# Power_Supply.net
KiCad netlist of a schematic drawn in Altium Designer
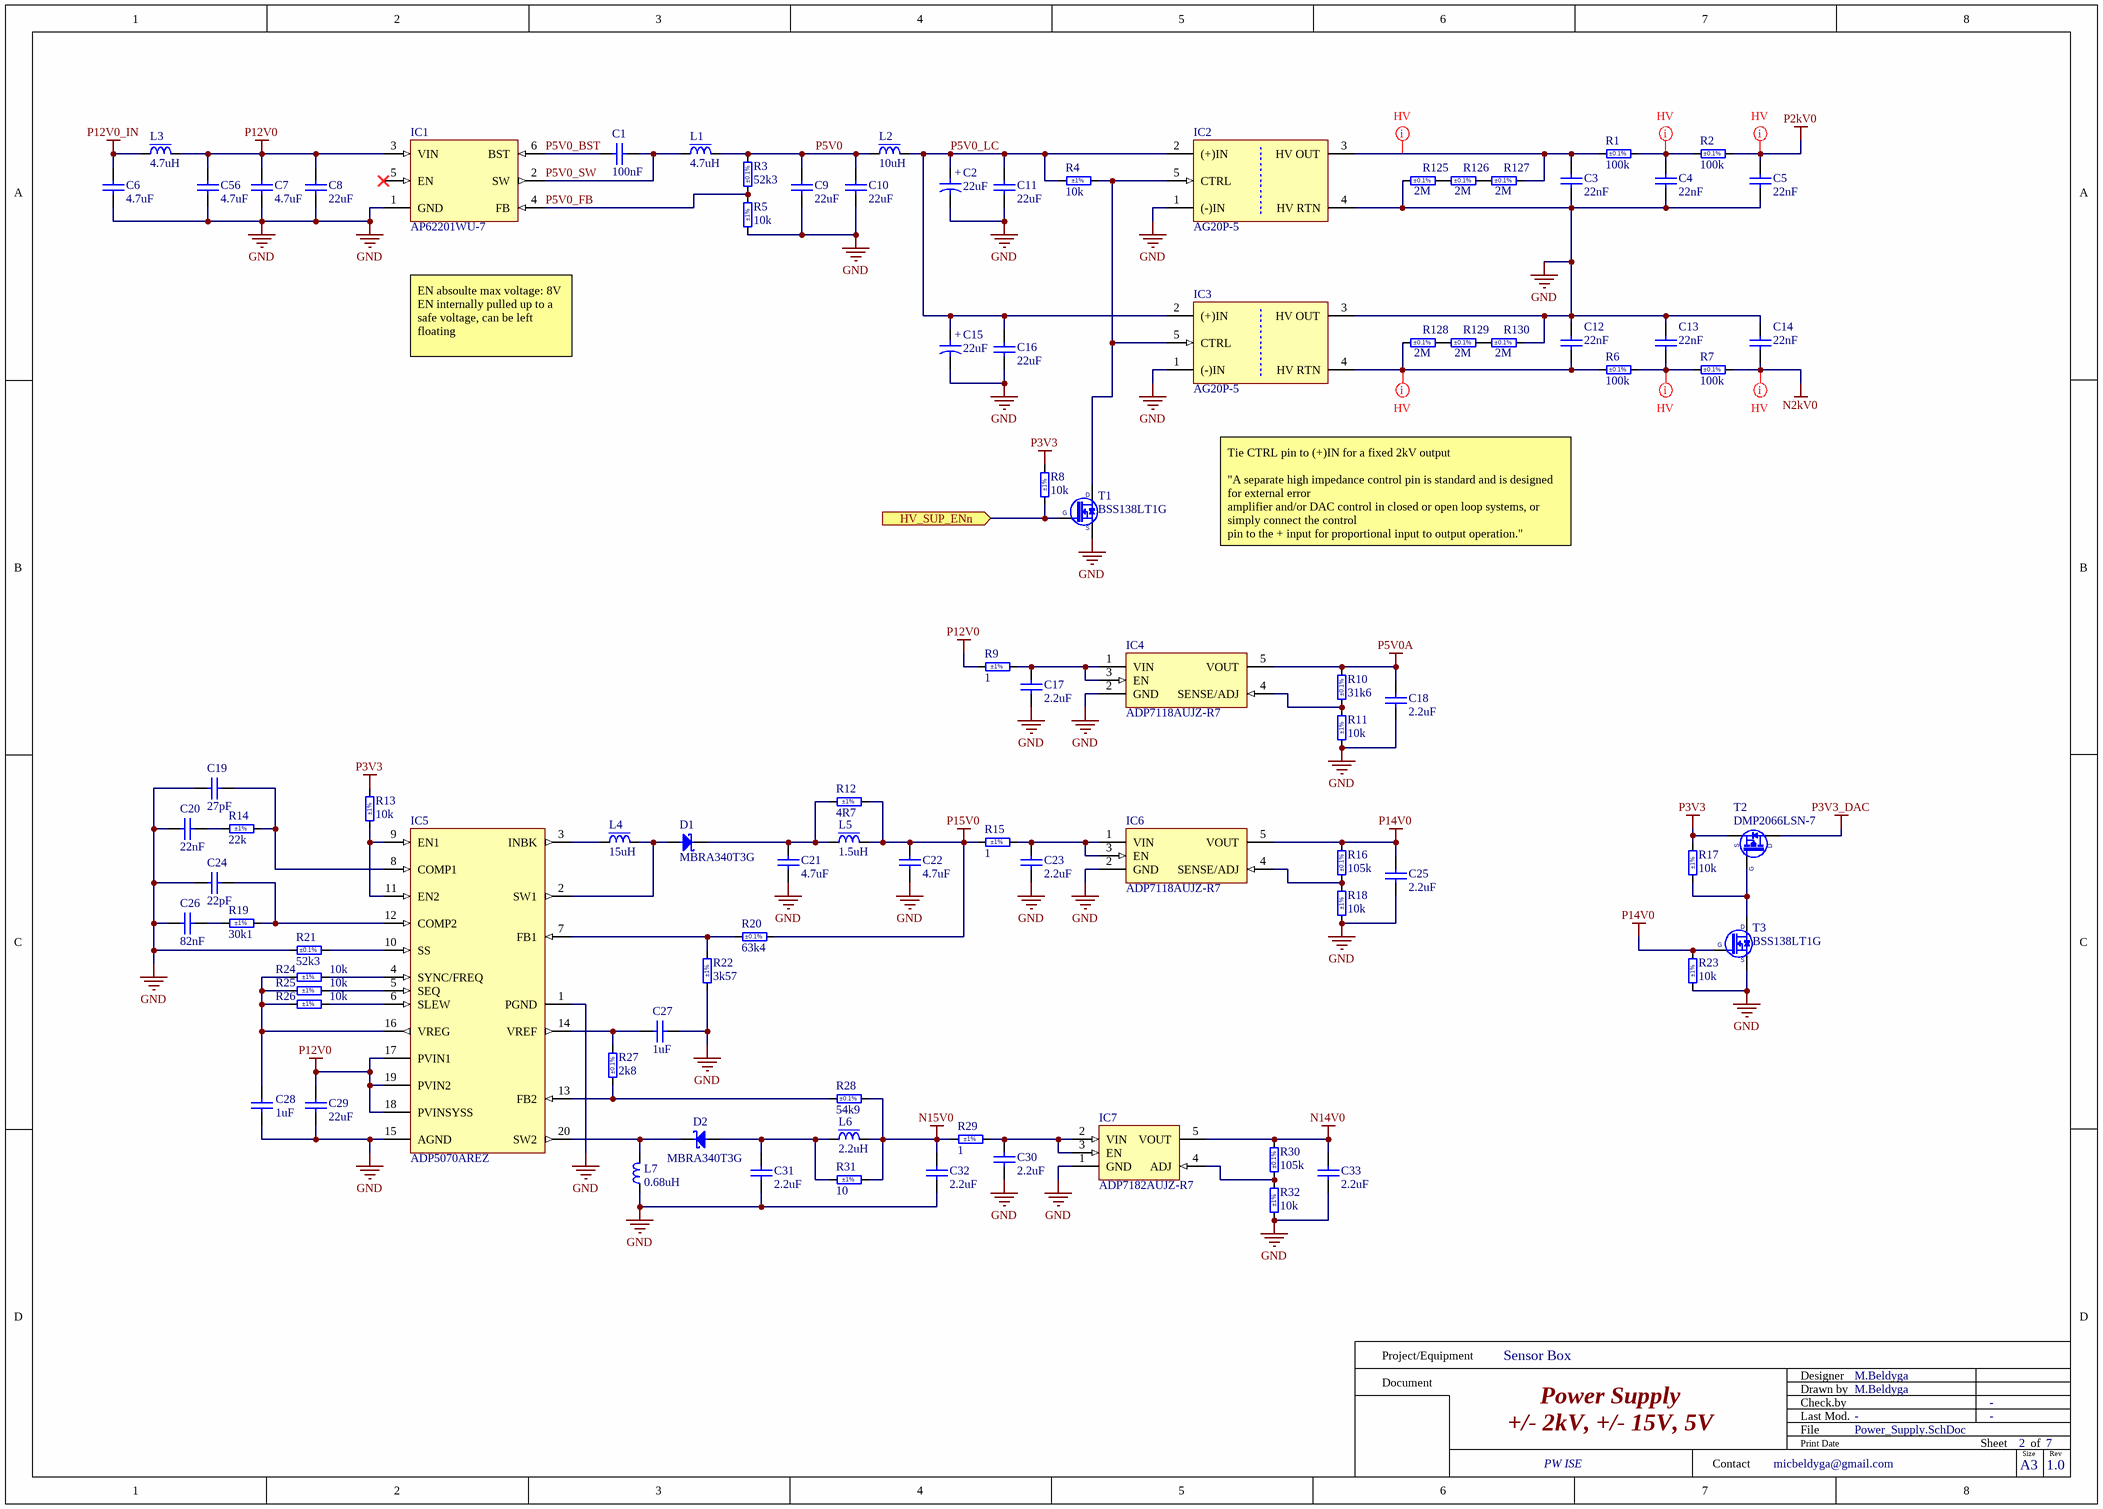
[diagram p0: Power_Supply.SchDoc]

(export (version "E")
  (design (tool "Eeschema 10.0.6"))
  (components
    (comp (ref "C1")
      (value "100nF")
      (footprint "CAPC1005X55N")
      (description "Non-polarised capacitor")
      (fields
        (field (name "PART NUMBER") "CC0402_100NF_50V_10%_X7R")
        (field (name "VOLTAGE") "50V")
        (field (name "AUTHOR") "CERN DEM MR")
      )
      (libsource (lib "Capacitors") (part "Capacitor - non polarized"))
    )
    (comp (ref "C2")
      (value "22uF")
      (footprint "CAPMP3528X210N")
      (description "Polarised capacitor")
      (fields
        (field (name "PART NUMBER") "CTE3528-21_22UF_20V_10%")
        (field (name "VOLTAGE") "20V")
        (field (name "AUTHOR") "CERN DEM JLC")
      )
      (libsource (lib "Capacitors") (part "Capacitor - polarized"))
    )
    (comp (ref "C3")
      (value "22nF")
      (footprint "CAPC5764X279N")
      (description "Non-polarised capacitor")
      (fields
        (field (name "PART NUMBER") "CC2225_22NF_2.5KV_10%_X7R")
        (field (name "VOLTAGE") "2.5KV")
        (field (name "AUTHOR") "CERN DEM JLC")
      )
      (libsource (lib "Capacitors") (part "Capacitor - non polarized"))
    )
    (comp (ref "C4")
      (value "22nF")
      (footprint "CAPC5764X279N")
      (description "Non-polarised capacitor")
      (fields
        (field (name "PART NUMBER") "CC2225_22NF_2.5KV_10%_X7R")
        (field (name "VOLTAGE") "2.5KV")
        (field (name "AUTHOR") "CERN DEM JLC")
      )
      (libsource (lib "Capacitors") (part "Capacitor - non polarized"))
    )
    (comp (ref "C5")
      (value "22nF")
      (footprint "CAPC5764X279N")
      (description "Non-polarised capacitor")
      (fields
        (field (name "PART NUMBER") "CC2225_22NF_2.5KV_10%_X7R")
        (field (name "VOLTAGE") "2.5KV")
        (field (name "AUTHOR") "CERN DEM JLC")
      )
      (libsource (lib "Capacitors") (part "Capacitor - non polarized"))
    )
    (comp (ref "C6")
      (value "4.7uF")
      (footprint "CAPC2012X145N")
      (description "Non-polarised capacitor")
      (fields
        (field (name "PART NUMBER") "CC0805_4.7UF_50V_10%_X7R")
        (field (name "VOLTAGE") "50V")
        (field (name "AUTHOR") "CERN DEM JMW")
      )
      (libsource (lib "Capacitors") (part "Capacitor - non polarized"))
    )
    (comp (ref "C7")
      (value "4.7uF")
      (footprint "CAPC2012X145N")
      (description "Non-polarised capacitor")
      (fields
        (field (name "PART NUMBER") "CC0805_4.7UF_50V_10%_X7R")
        (field (name "VOLTAGE") "50V")
        (field (name "AUTHOR") "CERN DEM JMW")
      )
      (libsource (lib "Capacitors") (part "Capacitor - non polarized"))
    )
    (comp (ref "C8")
      (value "22uF")
      (footprint "CAPC3216X180N")
      (description "Non-polarised capacitor")
      (fields
        (field (name "PART NUMBER") "CC1206_22UF_25V_20%_X5R")
        (field (name "VOLTAGE") "25V")
        (field (name "AUTHOR") "CERN DEM WB")
      )
      (libsource (lib "Capacitors") (part "Capacitor - non polarized"))
    )
    (comp (ref "C9")
      (value "22uF")
      (footprint "CAPC2012X135N")
      (description "Non-polarised capacitor")
      (fields
        (field (name "PART NUMBER") "CC0805_22UF_16V_10%_X5R")
        (field (name "VOLTAGE") "16V")
        (field (name "AUTHOR") "CERN DEM JLC")
      )
      (libsource (lib "Capacitors") (part "Capacitor - non polarized"))
    )
    (comp (ref "C10")
      (value "22uF")
      (footprint "CAPC2012X135N")
      (description "Non-polarised capacitor")
      (fields
        (field (name "PART NUMBER") "CC0805_22UF_16V_10%_X5R")
        (field (name "VOLTAGE") "16V")
        (field (name "AUTHOR") "CERN DEM JLC")
      )
      (libsource (lib "Capacitors") (part "Capacitor - non polarized"))
    )
    (comp (ref "C11")
      (value "22uF")
      (footprint "CAPC3216X180N")
      (description "Non-polarised capacitor")
      (fields
        (field (name "PART NUMBER") "CC1206_22UF_25V_20%_X5R")
        (field (name "VOLTAGE") "25V")
        (field (name "AUTHOR") "CERN DEM WB")
      )
      (libsource (lib "Capacitors") (part "Capacitor - non polarized"))
    )
    (comp (ref "C12")
      (value "22nF")
      (footprint "CAPC5764X279N")
      (description "Non-polarised capacitor")
      (fields
        (field (name "PART NUMBER") "CC2225_22NF_2.5KV_10%_X7R")
        (field (name "VOLTAGE") "2.5KV")
        (field (name "AUTHOR") "CERN DEM JLC")
      )
      (libsource (lib "Capacitors") (part "Capacitor - non polarized"))
    )
    (comp (ref "C13")
      (value "22nF")
      (footprint "CAPC5764X279N")
      (description "Non-polarised capacitor")
      (fields
        (field (name "PART NUMBER") "CC2225_22NF_2.5KV_10%_X7R")
        (field (name "VOLTAGE") "2.5KV")
        (field (name "AUTHOR") "CERN DEM JLC")
      )
      (libsource (lib "Capacitors") (part "Capacitor - non polarized"))
    )
    (comp (ref "C14")
      (value "22nF")
      (footprint "CAPC5764X279N")
      (description "Non-polarised capacitor")
      (fields
        (field (name "PART NUMBER") "CC2225_22NF_2.5KV_10%_X7R")
        (field (name "VOLTAGE") "2.5KV")
        (field (name "AUTHOR") "CERN DEM JLC")
      )
      (libsource (lib "Capacitors") (part "Capacitor - non polarized"))
    )
    (comp (ref "C15")
      (value "22uF")
      (footprint "CAPMP3528X210N")
      (description "Polarised capacitor")
      (fields
        (field (name "PART NUMBER") "CTE3528-21_22UF_20V_10%")
        (field (name "VOLTAGE") "20V")
        (field (name "AUTHOR") "CERN DEM JLC")
      )
      (libsource (lib "Capacitors") (part "Capacitor - polarized"))
    )
    (comp (ref "C16")
      (value "22uF")
      (footprint "CAPC3216X180N")
      (description "Non-polarised capacitor")
      (fields
        (field (name "PART NUMBER") "CC1206_22UF_25V_20%_X5R")
        (field (name "VOLTAGE") "25V")
        (field (name "AUTHOR") "CERN DEM WB")
      )
      (libsource (lib "Capacitors") (part "Capacitor - non polarized"))
    )
    (comp (ref "C17")
      (value "2.2uF")
      (footprint "CAPC1005X55N")
      (description "Non-polarised capacitor")
      (fields
        (field (name "PART NUMBER") "CC0402_2.2UF_16V_10%_X5R")
        (field (name "VOLTAGE") "16V")
        (field (name "AUTHOR") "CERN DEM BC")
      )
      (libsource (lib "Capacitors") (part "Capacitor - non polarized"))
    )
    (comp (ref "C18")
      (value "2.2uF")
      (footprint "CAPC1005X55N")
      (description "Non-polarised capacitor")
      (fields
        (field (name "PART NUMBER") "CC0402_2.2UF_16V_10%_X5R")
        (field (name "VOLTAGE") "16V")
        (field (name "AUTHOR") "CERN DEM BC")
      )
      (libsource (lib "Capacitors") (part "Capacitor - non polarized"))
    )
    (comp (ref "C19")
      (value "27pF")
      (footprint "CAPC1005X55N")
      (description "Non-polarised capacitor")
      (fields
        (field (name "PART NUMBER") "CC0402_27PF_50V_5%_C0G")
        (field (name "VOLTAGE") "50V")
        (field (name "AUTHOR") "CERN DEM JLC")
      )
      (libsource (lib "Capacitors") (part "Capacitor - non polarized"))
    )
    (comp (ref "C20")
      (value "22nF")
      (footprint "CAPC1005X55N")
      (description "Non-polarised capacitor")
      (fields
        (field (name "PART NUMBER") "CC0402_22NF_16V_10%_X7R")
        (field (name "VOLTAGE") "16V")
        (field (name "AUTHOR") "CERN DEM JLC")
      )
      (libsource (lib "Capacitors") (part "Capacitor - non polarized"))
    )
    (comp (ref "C21")
      (value "4.7uF")
      (footprint "CAPC2012X145N")
      (description "Non-polarised capacitor")
      (fields
        (field (name "PART NUMBER") "CC0805_4.7UF_50V_10%_X7R")
        (field (name "VOLTAGE") "50V")
        (field (name "AUTHOR") "CERN DEM JMW")
      )
      (libsource (lib "Capacitors") (part "Capacitor - non polarized"))
    )
    (comp (ref "C22")
      (value "4.7uF")
      (footprint "CAPC2012X145N")
      (description "Non-polarised capacitor")
      (fields
        (field (name "PART NUMBER") "CC0805_4.7UF_50V_10%_X7R")
        (field (name "VOLTAGE") "50V")
        (field (name "AUTHOR") "CERN DEM JMW")
      )
      (libsource (lib "Capacitors") (part "Capacitor - non polarized"))
    )
    (comp (ref "C23")
      (value "2.2uF")
      (footprint "CAPC1005X55N")
      (description "Non-polarised capacitor")
      (fields
        (field (name "PART NUMBER") "CC0402_2.2UF_16V_10%_X5R")
        (field (name "VOLTAGE") "16V")
        (field (name "AUTHOR") "CERN DEM BC")
      )
      (libsource (lib "Capacitors") (part "Capacitor - non polarized"))
    )
    (comp (ref "C24")
      (value "22pF")
      (footprint "CAPC1005X55N")
      (description "Non-polarised capacitor")
      (fields
        (field (name "PART NUMBER") "CC0402_22PF_50V_5%_C0G")
        (field (name "VOLTAGE") "50V")
        (field (name "AUTHOR") "CERN DEM JLC")
      )
      (libsource (lib "Capacitors") (part "Capacitor - non polarized"))
    )
    (comp (ref "C25")
      (value "2.2uF")
      (footprint "CAPC1005X55N")
      (description "Non-polarised capacitor")
      (fields
        (field (name "PART NUMBER") "CC0402_2.2UF_16V_10%_X5R")
        (field (name "VOLTAGE") "16V")
        (field (name "AUTHOR") "CERN DEM BC")
      )
      (libsource (lib "Capacitors") (part "Capacitor - non polarized"))
    )
    (comp (ref "C26")
      (value "82nF")
      (footprint "CAPC1608X87N")
      (description "Non-polarised capacitor")
      (fields
        (field (name "PART NUMBER") "CC0603_82NF_16V_10%_X7R")
        (field (name "VOLTAGE") "16V")
        (field (name "AUTHOR") "CERN DEM JLC")
      )
      (libsource (lib "Capacitors") (part "Capacitor - non polarized"))
    )
    (comp (ref "C27")
      (value "1uF")
      (footprint "CAPC1005X55N")
      (description "Non-polarised capacitor")
      (fields
        (field (name "PART NUMBER") "CC0402_1UF_16V_10%_X5R")
        (field (name "VOLTAGE") "16V")
        (field (name "AUTHOR") "CERN DEM JLC")
      )
      (libsource (lib "Capacitors") (part "Capacitor - non polarized"))
    )
    (comp (ref "C28")
      (value "1uF")
      (footprint "CAPC1005X55N")
      (description "Non-polarised capacitor")
      (fields
        (field (name "PART NUMBER") "CC0402_1UF_16V_10%_X5R")
        (field (name "VOLTAGE") "16V")
        (field (name "AUTHOR") "CERN DEM JLC")
      )
      (libsource (lib "Capacitors") (part "Capacitor - non polarized"))
    )
    (comp (ref "C29")
      (value "22uF")
      (footprint "CAPC3216X180N")
      (description "Non-polarised capacitor")
      (fields
        (field (name "PART NUMBER") "CC1206_22UF_25V_20%_X5R")
        (field (name "VOLTAGE") "25V")
        (field (name "AUTHOR") "CERN DEM WB")
      )
      (libsource (lib "Capacitors") (part "Capacitor - non polarized"))
    )
    (comp (ref "C30")
      (value "2.2uF")
      (footprint "CAPC1005X55N")
      (description "Non-polarised capacitor")
      (fields
        (field (name "PART NUMBER") "CC0402_2.2UF_16V_10%_X5R")
        (field (name "VOLTAGE") "16V")
        (field (name "AUTHOR") "CERN DEM BC")
      )
      (libsource (lib "Capacitors") (part "Capacitor - non polarized"))
    )
    (comp (ref "C31")
      (value "2.2uF")
      (footprint "CAPC2013X145N")
      (description "Non-polarised capacitor")
      (fields
        (field (name "PART NUMBER") "CC0805_2.2UF_35V_10%_X7R")
        (field (name "VOLTAGE") "35V")
        (field (name "AUTHOR") "CERN DEM HF")
      )
      (libsource (lib "Capacitors") (part "Capacitor - non polarized"))
    )
    (comp (ref "C32")
      (value "2.2uF")
      (footprint "CAPC2013X145N")
      (description "Non-polarised capacitor")
      (fields
        (field (name "PART NUMBER") "CC0805_2.2UF_35V_10%_X7R")
        (field (name "VOLTAGE") "35V")
        (field (name "AUTHOR") "CERN DEM HF")
      )
      (libsource (lib "Capacitors") (part "Capacitor - non polarized"))
    )
    (comp (ref "C33")
      (value "2.2uF")
      (footprint "CAPC1005X55N")
      (description "Non-polarised capacitor")
      (fields
        (field (name "PART NUMBER") "CC0402_2.2UF_16V_10%_X5R")
        (field (name "VOLTAGE") "16V")
        (field (name "AUTHOR") "CERN DEM BC")
      )
      (libsource (lib "Capacitors") (part "Capacitor - non polarized"))
    )
    (comp (ref "C56")
      (value "4.7uF")
      (footprint "CAPC2012X145N")
      (description "Non-polarised capacitor")
      (fields
        (field (name "PART NUMBER") "CC0805_4.7UF_50V_10%_X7R")
        (field (name "VOLTAGE") "50V")
        (field (name "AUTHOR") "CERN DEM JMW")
      )
      (libsource (lib "Capacitors") (part "Capacitor - non polarized"))
    )
    (comp (ref "D1")
      (value "MBRA340T3G")
      (footprint "DIOM5226X220N")
      (description "Schottky Diode")
      (fields
        (field (name "VOLTAGE") "40V")
        (field (name "POWER") "3A")
        (field (name "AUTHOR") "CERN DEM JLC")
      )
      (libsource (lib "ICs And Semiconductors") (part "Diode Schottky"))
    )
    (comp (ref "D2")
      (value "MBRA340T3G")
      (footprint "DIOM5226X220N")
      (description "Schottky Diode")
      (fields
        (field (name "VOLTAGE") "40V")
        (field (name "POWER") "3A")
        (field (name "AUTHOR") "CERN DEM JLC")
      )
      (libsource (lib "ICs And Semiconductors") (part "Diode Schottky"))
    )
    (comp (ref "IC1")
      (value "AP62201WU-7")
      (footprint "SOT95P280X100-6N")
      (description "4.2V TO 18V INPUT, 2A LOW IQ SYNCHRONOUS BUCK CONVERTER")
      (fields
        (field (name "MANUFACTURER") "DIODES INCORPORATED")
        (field (name "MANUFACTURER PART NUMBER") "AP62201WU")
        (field (name "AUTHOR") "CERN DEM HF")
      )
      (libsource (lib "ICs And Semiconductors") (part "AP62201WU"))
    )
    (comp (ref "IC2")
      (value "AG20P-5")
      (footprint "DCDC_XPPOWER_AG0-2KV")
      (description "XP POWER, AG Series, DC/HVDC Converter")
      (fields (field (name "MANUFACTURER") "XP POWER") (field (name "AUTHOR") "CERN DEM BC"))
      (libsource (lib "ICs And Semiconductors") (part "DCDC_XPPOWER_AG"))
    )
    (comp (ref "IC3")
      (value "AG20P-5")
      (footprint "DCDC_XPPOWER_AG0-2KV")
      (description "XP POWER, AG Series, DC/HVDC Converter")
      (fields (field (name "MANUFACTURER") "XP POWER") (field (name "AUTHOR") "CERN DEM BC"))
      (libsource (lib "ICs And Semiconductors") (part "DCDC_XPPOWER_AG"))
    )
    (comp (ref "IC4")
      (value "ADP7118AUJZ-R7")
      (footprint "SOT95P280X90-5N")
      (description "Adjustable Positive LDO Regulator, 1.2V Min, 20V Max, 0.42V Dropout, CMOS, PDSO5")
      (fields (field (name "MANUFACTURER") "Analog Devices"))
      (libsource (lib "mb") (part "ADP7118AUJZ-R7"))
    )
    (comp (ref "IC5")
      (value "ADP5070AREZ")
      (footprint "SOP65P640X120-21N-R305X425")
      (description "1A/0.6A, DC-to-DC Switching Regulator with Independent Positive and Negative Outputs")
      (fields
        (field (name "MANUFACTURER") "ANALOG DEVICES")
        (field (name "MANUFACTURER PART NUMBER") "ADP5070ARE")
        (field (name "AUTHOR") "CERN DEM JLC")
      )
      (libsource (lib "ICs And Semiconductors") (part "ADP5070AREZ"))
    )
    (comp (ref "IC6")
      (value "ADP7118AUJZ-R7")
      (footprint "SOT95P280X90-5N")
      (description "Adjustable Positive LDO Regulator, 1.2V Min, 20V Max, 0.42V Dropout, CMOS, PDSO5")
      (fields (field (name "MANUFACTURER") "Analog Devices"))
      (libsource (lib "mb") (part "ADP7118AUJZ-R7"))
    )
    (comp (ref "IC7")
      (value "ADP7182AUJZ-R7")
      (footprint "SOT95P280X90-5N")
      (description "-1.22V to -27V, -200mA, Adjustable, Low Noise, Negative Linear Regulator")
      (fields
        (field (name "MANUFACTURER") "ANALOG DEVICES")
        (field (name "MANUFACTURER PART NUMBER") "ADP7182AUJ")
        (field (name "AUTHOR") "CERN DEM JLC")
      )
      (libsource (lib "ICs And Semiconductors") (part "ADP7182AUJZ-R7"))
    )
    (comp (ref "L1")
      (value "4.7uH")
      (footprint "IND_WURTH_WE-SPC-4838")
      (description "Inductor With Core")
      (fields
        (field (name "PART NUMBER") "IND_4.7UH_20%_WURTH_WE-SPC_74408943047")
        (field (name "POWER") "2.2A")
        (field (name "AUTHOR") "CERN DEM JLC")
      )
      (libsource (lib "Inductors & Transformers") (part "Inductor With Magnetic core"))
    )
    (comp (ref "L2")
      (value "10uH")
      (footprint "IND_BOURNS_PM43")
      (description "Inductor With Core")
      (fields
        (field (name "PART NUMBER") "IND_10UH_20%_BOURNS_PM43")
        (field (name "POWER") "1.15A")
        (field (name "AUTHOR") "CERN DEM JLC")
      )
      (libsource (lib "Inductors & Transformers") (part "Inductor With Magnetic core"))
    )
    (comp (ref "L3")
      (value "4.7uH")
      (footprint "IND_WURTH_WE-SPC-4838")
      (description "Inductor With Core")
      (fields
        (field (name "PART NUMBER") "IND_4.7UH_20%_WURTH_WE-SPC_74408943047")
        (field (name "POWER") "2.2A")
        (field (name "AUTHOR") "CERN DEM JLC")
      )
      (libsource (lib "Inductors & Transformers") (part "Inductor With Magnetic core"))
    )
    (comp (ref "L4")
      (value "15uH")
      (footprint "IND_WURTH_WE-SPC-4838")
      (description "Inductor With Core")
      (fields
        (field (name "PART NUMBER") "IND_15UH_20%_WURTH_WE-SPC_74408943150")
        (field (name "POWER") "1.4A")
        (field (name "AUTHOR") "CERN DEM MR")
      )
      (libsource (lib "Inductors & Transformers") (part "Inductor With Magnetic core"))
    )
    (comp (ref "L5")
      (value "1.5uH")
      (footprint "IND_COILCRAFT_XAL4020")
      (description "Inductor With Core")
      (fields
        (field (name "PART NUMBER") "IND_1.5UH_20%_COILCRAFT_XAL4020")
        (field (name "POWER") "5.2A")
        (field (name "AUTHOR") "CERN DEM BC")
      )
      (libsource (lib "Inductors & Transformers") (part "Inductor With Magnetic core"))
    )
    (comp (ref "L6")
      (value "2.2uH")
      (footprint "IND_MURATA_LQH44PN_P0")
      (description "Inductor With Core")
      (fields
        (field (name "PART NUMBER") "IND_2.2UH_20%_MURATA_LQH44PN2R2MP0L")
        (field (name "POWER") "1.8A")
        (field (name "AUTHOR") "CERN DEM JLC")
      )
      (libsource (lib "Inductors & Transformers") (part "Inductor With Magnetic core"))
    )
    (comp (ref "L7")
      (value "0.68uH")
      (footprint "IND_BOURNS_SRP3212")
      (description "Inductor")
      (fields
        (field (name "PART NUMBER") "IND_0.68UH_20%_BOURNS_SRP3212")
        (field (name "POWER") "6.2A")
        (field (name "AUTHOR") "CERN DEM HF")
      )
      (libsource (lib "Inductors & Transformers") (part "Inductor"))
    )
    (comp (ref "R1")
      (value "100k")
      (footprint "RESC3216X50N")
      (description "Resistor - 0.1%")
      (fields
        (field (name "TOLERANCE") "±0.1%")
        (field (name "PART NUMBER") "R1206_100K_0.1%_0.4W_25PPM_VISHAY_PAT")
        (field (name "POWER") "0.4W")
        (field (name "AUTHOR") "CERN DEM MR")
      )
      (libsource (lib "Resistors") (part "Resistor - 0.1%"))
    )
    (comp (ref "R2")
      (value "100k")
      (footprint "RESC3216X50N")
      (description "Resistor - 0.1%")
      (fields
        (field (name "TOLERANCE") "±0.1%")
        (field (name "PART NUMBER") "R1206_100K_0.1%_0.4W_25PPM_VISHAY_PAT")
        (field (name "POWER") "0.4W")
        (field (name "AUTHOR") "CERN DEM MR")
      )
      (libsource (lib "Resistors") (part "Resistor - 0.1%"))
    )
    (comp (ref "R3")
      (value "52k3")
      (footprint "RESC1608X55N")
      (description "Resistor - 0.1%")
      (fields
        (field (name "TOLERANCE") "±0.1%")
        (field (name "PART NUMBER") "R0603_52K3_0.1%_0.063W_10PPM")
        (field (name "POWER") "0.063W")
        (field (name "AUTHOR") "CERN DEM JLC")
      )
      (libsource (lib "Resistors") (part "Resistor - 0.1%"))
    )
    (comp (ref "R4")
      (value "10k")
      (footprint "RESC1005X40N")
      (description "Resistor - 1%")
      (fields
        (field (name "TOLERANCE") "±1%")
        (field (name "PART NUMBER") "R0402_10K_1%_0.0625W_100PPM")
        (field (name "POWER") "0.0625W")
        (field (name "AUTHOR") "CERN DEM JLC")
      )
      (libsource (lib "Resistors") (part "Resistor - 1%"))
    )
    (comp (ref "R5")
      (value "10k")
      (footprint "RESC1005X40N")
      (description "Resistor - 1%")
      (fields
        (field (name "TOLERANCE") "±1%")
        (field (name "PART NUMBER") "R0402_10K_1%_0.0625W_100PPM")
        (field (name "POWER") "0.0625W")
        (field (name "AUTHOR") "CERN DEM JLC")
      )
      (libsource (lib "Resistors") (part "Resistor - 1%"))
    )
    (comp (ref "R6")
      (value "100k")
      (footprint "RESC3216X50N")
      (description "Resistor - 0.1%")
      (fields
        (field (name "TOLERANCE") "±0.1%")
        (field (name "PART NUMBER") "R1206_100K_0.1%_0.4W_25PPM_VISHAY_PAT")
        (field (name "POWER") "0.4W")
        (field (name "AUTHOR") "CERN DEM MR")
      )
      (libsource (lib "Resistors") (part "Resistor - 0.1%"))
    )
    (comp (ref "R7")
      (value "100k")
      (footprint "RESC3216X50N")
      (description "Resistor - 0.1%")
      (fields
        (field (name "TOLERANCE") "±0.1%")
        (field (name "PART NUMBER") "R1206_100K_0.1%_0.4W_25PPM_VISHAY_PAT")
        (field (name "POWER") "0.4W")
        (field (name "AUTHOR") "CERN DEM MR")
      )
      (libsource (lib "Resistors") (part "Resistor - 0.1%"))
    )
    (comp (ref "R8")
      (value "10k")
      (footprint "RESC1005X40N")
      (description "Resistor - 1%")
      (fields
        (field (name "TOLERANCE") "±1%")
        (field (name "PART NUMBER") "R0402_10K_1%_0.0625W_100PPM")
        (field (name "POWER") "0.0625W")
        (field (name "AUTHOR") "CERN DEM JLC")
      )
      (libsource (lib "Resistors") (part "Resistor - 1%"))
    )
    (comp (ref "R9")
      (value "1")
      (footprint "RESC1005X40N")
      (description "Resistor - 1%")
      (fields
        (field (name "TOLERANCE") "±1%")
        (field (name "PART NUMBER") "R0402_1R_1%_0.0625W_200PPM")
        (field (name "POWER") "0.0625W")
        (field (name "AUTHOR") "CERN DEM JLC")
      )
      (libsource (lib "Resistors") (part "Resistor - 1%"))
    )
    (comp (ref "R10")
      (value "31k6")
      (footprint "RESC1005X35N")
      (description "Resistor - 0.1%")
      (fields
        (field (name "TOLERANCE") "±0.1%")
        (field (name "PART NUMBER") "R0402_31K6_0.1%_0.063W_25PPM_YAGEO_RT")
        (field (name "POWER") "0.063W")
        (field (name "AUTHOR") "CERN DEM BC")
      )
      (libsource (lib "Resistors") (part "Resistor - 0.1%"))
    )
    (comp (ref "R11")
      (value "10k")
      (footprint "RESC1005X40N")
      (description "Resistor - 1%")
      (fields
        (field (name "TOLERANCE") "±1%")
        (field (name "PART NUMBER") "R0402_10K_1%_0.0625W_100PPM")
        (field (name "POWER") "0.0625W")
        (field (name "AUTHOR") "CERN DEM JLC")
      )
      (libsource (lib "Resistors") (part "Resistor - 1%"))
    )
    (comp (ref "R12")
      (value "4R7")
      (footprint "RESC1005X40N")
      (description "Resistor - 1%")
      (fields
        (field (name "TOLERANCE") "±1%")
        (field (name "PART NUMBER") "R0402_4R7_1%_0.0625W_200PPM")
        (field (name "POWER") "0.0625W")
        (field (name "AUTHOR") "CERN DEM JLC")
      )
      (libsource (lib "Resistors") (part "Resistor - 1%"))
    )
    (comp (ref "R13")
      (value "10k")
      (footprint "RESC1005X40N")
      (description "Resistor - 1%")
      (fields
        (field (name "TOLERANCE") "±1%")
        (field (name "PART NUMBER") "R0402_10K_1%_0.0625W_100PPM")
        (field (name "POWER") "0.0625W")
        (field (name "AUTHOR") "CERN DEM JLC")
      )
      (libsource (lib "Resistors") (part "Resistor - 1%"))
    )
    (comp (ref "R14")
      (value "22k")
      (footprint "RESC1005X40N")
      (description "Resistor - 1%")
      (fields
        (field (name "TOLERANCE") "±1%")
        (field (name "PART NUMBER") "R0402_22K_1%_0.0625W_100PPM")
        (field (name "POWER") "0.0625W")
        (field (name "AUTHOR") "CERN DEM JLC")
      )
      (libsource (lib "Resistors") (part "Resistor - 1%"))
    )
    (comp (ref "R15")
      (value "1")
      (footprint "RESC1005X40N")
      (description "Resistor - 1%")
      (fields
        (field (name "TOLERANCE") "±1%")
        (field (name "PART NUMBER") "R0402_1R_1%_0.0625W_200PPM")
        (field (name "POWER") "0.0625W")
        (field (name "AUTHOR") "CERN DEM JLC")
      )
      (libsource (lib "Resistors") (part "Resistor - 1%"))
    )
    (comp (ref "R16")
      (value "105k")
      (footprint "RESC1608X55N")
      (description "Resistor - 0.1%")
      (fields
        (field (name "TOLERANCE") "±0.1%")
        (field (name "PART NUMBER") "R0603_105K_0.1%_0.063W_10PPM")
        (field (name "POWER") "0.063W")
        (field (name "AUTHOR") "CERN DEM JLC")
      )
      (libsource (lib "Resistors") (part "Resistor - 0.1%"))
    )
    (comp (ref "R17")
      (value "10k")
      (footprint "RESC1005X40N")
      (description "Resistor - 1%")
      (fields
        (field (name "TOLERANCE") "±1%")
        (field (name "PART NUMBER") "R0402_10K_1%_0.0625W_100PPM")
        (field (name "POWER") "0.0625W")
        (field (name "AUTHOR") "CERN DEM JLC")
      )
      (libsource (lib "Resistors") (part "Resistor - 1%"))
    )
    (comp (ref "R18")
      (value "10k")
      (footprint "RESC1005X40N")
      (description "Resistor - 1%")
      (fields
        (field (name "TOLERANCE") "±1%")
        (field (name "PART NUMBER") "R0402_10K_1%_0.0625W_100PPM")
        (field (name "POWER") "0.0625W")
        (field (name "AUTHOR") "CERN DEM JLC")
      )
      (libsource (lib "Resistors") (part "Resistor - 1%"))
    )
    (comp (ref "R19")
      (value "30k1")
      (footprint "RESC1005X40N")
      (description "Resistor - 1%")
      (fields
        (field (name "TOLERANCE") "±1%")
        (field (name "PART NUMBER") "R0402_30K1_1%_0.0625W_100PPM")
        (field (name "POWER") "0.0625W")
        (field (name "AUTHOR") "CERN DEM BC")
      )
      (libsource (lib "Resistors") (part "Resistor - 1%"))
    )
    (comp (ref "R20")
      (value "63k4")
      (footprint "RESC1608X55N")
      (description "Resistor - 0.1%")
      (fields
        (field (name "TOLERANCE") "±0.1%")
        (field (name "PART NUMBER") "R0603_63K4_0.1%_0.063W_10PPM")
        (field (name "POWER") "0.063W")
        (field (name "AUTHOR") "CERN DEM JLC")
      )
      (libsource (lib "Resistors") (part "Resistor - 0.1%"))
    )
    (comp (ref "R21")
      (value "52k3")
      (footprint "RESC1608X55N")
      (description "Resistor - 0.1%")
      (fields
        (field (name "TOLERANCE") "±0.1%")
        (field (name "PART NUMBER") "R0603_52K3_0.1%_0.063W_10PPM")
        (field (name "POWER") "0.063W")
        (field (name "AUTHOR") "CERN DEM JLC")
      )
      (libsource (lib "Resistors") (part "Resistor - 0.1%"))
    )
    (comp (ref "R22")
      (value "3k57")
      (footprint "RESC1608X55N")
      (description "Resistor - 1%")
      (fields
        (field (name "TOLERANCE") "±1%")
        (field (name "PART NUMBER") "R0603_3K57_1%_0.063W_50PPM")
        (field (name "POWER") "0.063W")
        (field (name "AUTHOR") "CERN DEM JLC")
      )
      (libsource (lib "Resistors") (part "Resistor - 1%"))
    )
    (comp (ref "R23")
      (value "10k")
      (footprint "RESC1005X40N")
      (description "Resistor - 1%")
      (fields
        (field (name "TOLERANCE") "±1%")
        (field (name "PART NUMBER") "R0402_10K_1%_0.0625W_100PPM")
        (field (name "POWER") "0.0625W")
        (field (name "AUTHOR") "CERN DEM JLC")
      )
      (libsource (lib "Resistors") (part "Resistor - 1%"))
    )
    (comp (ref "R24")
      (value "10k")
      (footprint "RESC1005X40N")
      (description "Resistor - 1%")
      (fields
        (field (name "TOLERANCE") "±1%")
        (field (name "PART NUMBER") "R0402_10K_1%_0.0625W_100PPM")
        (field (name "POWER") "0.0625W")
        (field (name "AUTHOR") "CERN DEM JLC")
      )
      (libsource (lib "Resistors") (part "Resistor - 1%"))
    )
    (comp (ref "R25")
      (value "10k")
      (footprint "RESC1005X40N")
      (description "Resistor - 1%")
      (fields
        (field (name "TOLERANCE") "±1%")
        (field (name "PART NUMBER") "R0402_10K_1%_0.0625W_100PPM")
        (field (name "POWER") "0.0625W")
        (field (name "AUTHOR") "CERN DEM JLC")
      )
      (libsource (lib "Resistors") (part "Resistor - 1%"))
    )
    (comp (ref "R26")
      (value "10k")
      (footprint "RESC1005X40N")
      (description "Resistor - 1%")
      (fields
        (field (name "TOLERANCE") "±1%")
        (field (name "PART NUMBER") "R0402_10K_1%_0.0625W_100PPM")
        (field (name "POWER") "0.0625W")
        (field (name "AUTHOR") "CERN DEM JLC")
      )
      (libsource (lib "Resistors") (part "Resistor - 1%"))
    )
    (comp (ref "R27")
      (value "2k8")
      (footprint "RESC1608X55N")
      (description "Resistor - 0.1%")
      (fields
        (field (name "TOLERANCE") "±0.1%")
        (field (name "PART NUMBER") "R0603_2K8_0.1%_0.063W_10PPM")
        (field (name "POWER") "0.063W")
        (field (name "AUTHOR") "CERN DEM JLC")
      )
      (libsource (lib "Resistors") (part "Resistor - 0.1%"))
    )
    (comp (ref "R28")
      (value "54k9")
      (footprint "RESC1608X55N")
      (description "Resistor - 0.1%")
      (fields
        (field (name "TOLERANCE") "±0.1%")
        (field (name "PART NUMBER") "R0603_54K9_0.1%_0.063W_10PPM")
        (field (name "POWER") "0.063W")
        (field (name "AUTHOR") "CERN DEM JLC")
      )
      (libsource (lib "Resistors") (part "Resistor - 0.1%"))
    )
    (comp (ref "R29")
      (value "1")
      (footprint "RESC1005X40N")
      (description "Resistor - 1%")
      (fields
        (field (name "TOLERANCE") "±1%")
        (field (name "PART NUMBER") "R0402_1R_1%_0.0625W_200PPM")
        (field (name "POWER") "0.0625W")
        (field (name "AUTHOR") "CERN DEM JLC")
      )
      (libsource (lib "Resistors") (part "Resistor - 1%"))
    )
    (comp (ref "R30")
      (value "105k")
      (footprint "RESC1608X55N")
      (description "Resistor - 0.1%")
      (fields
        (field (name "TOLERANCE") "±0.1%")
        (field (name "PART NUMBER") "R0603_105K_0.1%_0.063W_10PPM")
        (field (name "POWER") "0.063W")
        (field (name "AUTHOR") "CERN DEM JLC")
      )
      (libsource (lib "Resistors") (part "Resistor - 0.1%"))
    )
    (comp (ref "R31")
      (value "10")
      (footprint "RESC1005X40N")
      (description "Resistor - 1%")
      (fields
        (field (name "TOLERANCE") "±1%")
        (field (name "PART NUMBER") "R0402_10R_1%_0.0625W_200PPM")
        (field (name "POWER") "0.0625W")
        (field (name "AUTHOR") "CERN DEM JLC")
      )
      (libsource (lib "Resistors") (part "Resistor - 1%"))
    )
    (comp (ref "R32")
      (value "10k")
      (footprint "RESC1005X40N")
      (description "Resistor - 1%")
      (fields
        (field (name "TOLERANCE") "±1%")
        (field (name "PART NUMBER") "R0402_10K_1%_0.0625W_100PPM")
        (field (name "POWER") "0.0625W")
        (field (name "AUTHOR") "CERN DEM JLC")
      )
      (libsource (lib "Resistors") (part "Resistor - 1%"))
    )
    (comp (ref "R125")
      (value "2M")
      (footprint "RESC5025X65N")
      (description "RES, HV, 2010, 2 Mohm, 0.1%, 25 ppm, 1W")
      (fields
        (field (name "PART NUMBER") "R1210_2M0_0.1%_1/3W_25ppm")
        (field (name "POWER") "1/3W")
        (field (name "TOLERANCE") "±0.1%")
        (field (name "AUTHOR") "GK")
      )
      (libsource (lib "Passives_RC") (part "R1210_2M0_0.1%_1/3W_25ppm"))
    )
    (comp (ref "R126")
      (value "2M")
      (footprint "RESC5025X65N")
      (description "RES, HV, 2010, 2 Mohm, 0.1%, 25 ppm, 1W")
      (fields
        (field (name "PART NUMBER") "R1210_2M0_0.1%_1/3W_25ppm")
        (field (name "POWER") "1/3W")
        (field (name "TOLERANCE") "±0.1%")
        (field (name "AUTHOR") "GK")
      )
      (libsource (lib "Passives_RC") (part "R1210_2M0_0.1%_1/3W_25ppm"))
    )
    (comp (ref "R127")
      (value "2M")
      (footprint "RESC5025X65N")
      (description "RES, HV, 2010, 2 Mohm, 0.1%, 25 ppm, 1W")
      (fields
        (field (name "PART NUMBER") "R1210_2M0_0.1%_1/3W_25ppm")
        (field (name "POWER") "1/3W")
        (field (name "TOLERANCE") "±0.1%")
        (field (name "AUTHOR") "GK")
      )
      (libsource (lib "Passives_RC") (part "R1210_2M0_0.1%_1/3W_25ppm"))
    )
    (comp (ref "R128")
      (value "2M")
      (footprint "RESC5025X65N")
      (description "RES, HV, 2010, 2 Mohm, 0.1%, 25 ppm, 1W")
      (fields
        (field (name "PART NUMBER") "R1210_2M0_0.1%_1/3W_25ppm")
        (field (name "POWER") "1/3W")
        (field (name "TOLERANCE") "±0.1%")
        (field (name "AUTHOR") "GK")
      )
      (libsource (lib "Passives_RC") (part "R1210_2M0_0.1%_1/3W_25ppm"))
    )
    (comp (ref "R129")
      (value "2M")
      (footprint "RESC5025X65N")
      (description "RES, HV, 2010, 2 Mohm, 0.1%, 25 ppm, 1W")
      (fields
        (field (name "PART NUMBER") "R1210_2M0_0.1%_1/3W_25ppm")
        (field (name "POWER") "1/3W")
        (field (name "TOLERANCE") "±0.1%")
        (field (name "AUTHOR") "GK")
      )
      (libsource (lib "Passives_RC") (part "R1210_2M0_0.1%_1/3W_25ppm"))
    )
    (comp (ref "R130")
      (value "2M")
      (footprint "RESC5025X65N")
      (description "RES, HV, 2010, 2 Mohm, 0.1%, 25 ppm, 1W")
      (fields
        (field (name "PART NUMBER") "R1210_2M0_0.1%_1/3W_25ppm")
        (field (name "POWER") "1/3W")
        (field (name "TOLERANCE") "±0.1%")
        (field (name "AUTHOR") "GK")
      )
      (libsource (lib "Passives_RC") (part "R1210_2M0_0.1%_1/3W_25ppm"))
    )
    (comp (ref "T1")
      (value "BSS138LT1G")
      (footprint "SOT95P240X110-3N")
      (description "N-CHANNEL MOSFET WITH DIODE")
      (fields
        (field (name "MANUFACTURER") "ON SEMICONDUCTOR")
        (field (name "MANUFACTURER PART NUMBER") "BSS138L")
        (field (name "AUTHOR") "CERN DEM JLC")
      )
      (libsource (lib "ICs And Semiconductors") (part "N-MOSFET-D 1G 2S 3D"))
    )
    (comp (ref "T2")
      (value "DMP2066LSN-7")
      (footprint "SOT95P285X140-3N")
      (description "P-CHANNEL MOSFET WITH DIODE")
      (fields (field (name "MANUFACTURER") "DIODES INCORPORATED") (field (name "AUTHOR") "CERN DEM JLC"))
      (libsource (lib "ICs And Semiconductors") (part "P-MOSFET-D 1G 2S 3D"))
    )
    (comp (ref "T3")
      (value "BSS138LT1G")
      (footprint "SOT95P240X110-3N")
      (description "N-CHANNEL MOSFET WITH DIODE")
      (fields
        (field (name "MANUFACTURER") "ON SEMICONDUCTOR")
        (field (name "MANUFACTURER PART NUMBER") "BSS138L")
        (field (name "AUTHOR") "CERN DEM JLC")
      )
      (libsource (lib "ICs And Semiconductors") (part "N-MOSFET-D 1G 2S 3D"))
    )
  )
  (nets
    (net (code "1") (name "/HV_SUP_ENn") (class "Default")
      (node (ref "R8") (pin "1") (pinfunction "1_1") (pintype "passive"))
      (node (ref "T1") (pin "1") (pinfunction "G_1") (pintype "passive"))
    )
    (net (code "2") (name "/P5V0") (class "Default")
      (node (ref "C10") (pin "2") (pinfunction "2_2") (pintype "passive"))
      (node (ref "C9") (pin "2") (pinfunction "2_2") (pintype "passive"))
      (node (ref "L1") (pin "2") (pinfunction "2_2") (pintype "passive"))
      (node (ref "L2") (pin "1") (pinfunction "1_1") (pintype "passive"))
      (node (ref "R3") (pin "2") (pinfunction "2_2") (pintype "passive"))
    )
    (net (code "3") (name "/P5V0_BST") (class "Default")
      (node (ref "C1") (pin "1") (pinfunction "1_1") (pintype "passive"))
      (node (ref "IC1") (pin "6") (pinfunction "BST_6") (pintype "input"))
    )
    (net (code "4") (name "/P5V0_FB") (class "Default")
      (node (ref "IC1") (pin "4") (pinfunction "FB_4") (pintype "input"))
      (node (ref "R3") (pin "1") (pinfunction "1_1") (pintype "passive"))
      (node (ref "R5") (pin "2") (pinfunction "2_2") (pintype "passive"))
    )
    (net (code "5") (name "/P5V0_LC") (class "Default")
      (node (ref "C11") (pin "2") (pinfunction "2_2") (pintype "passive"))
      (node (ref "C15") (pin "1") (pinfunction "1_1") (pintype "passive"))
      (node (ref "C16") (pin "2") (pinfunction "2_2") (pintype "passive"))
      (node (ref "C2") (pin "1") (pinfunction "1_1") (pintype "passive"))
      (node (ref "IC2") (pin "2") (pinfunction "(+)IN_2") (pintype "power_in"))
      (node (ref "IC3") (pin "2") (pinfunction "(+)IN_2") (pintype "power_in"))
      (node (ref "L2") (pin "2") (pinfunction "2_2") (pintype "passive"))
      (node (ref "R4") (pin "1") (pinfunction "1_1") (pintype "passive"))
    )
    (net (code "6") (name "/P5V0_SW") (class "Default")
      (node (ref "C1") (pin "2") (pinfunction "2_2") (pintype "passive"))
      (node (ref "IC1") (pin "2") (pinfunction "SW_2") (pintype "output"))
      (node (ref "L1") (pin "1") (pinfunction "1_1") (pintype "passive"))
    )
    (net (code "7") (name "GND") (class "Default")
      (node (ref "C10") (pin "1") (pinfunction "1_1") (pintype "passive"))
      (node (ref "C11") (pin "1") (pinfunction "1_1") (pintype "passive"))
      (node (ref "C12") (pin "2") (pinfunction "2_2") (pintype "passive"))
      (node (ref "C13") (pin "2") (pinfunction "2_2") (pintype "passive"))
      (node (ref "C14") (pin "2") (pinfunction "2_2") (pintype "passive"))
      (node (ref "C15") (pin "2") (pinfunction "2_2") (pintype "passive"))
      (node (ref "C16") (pin "1") (pinfunction "1_1") (pintype "passive"))
      (node (ref "C17") (pin "1") (pinfunction "1_1") (pintype "passive"))
      (node (ref "C18") (pin "1") (pinfunction "1_1") (pintype "passive"))
      (node (ref "C19") (pin "1") (pinfunction "1_1") (pintype "passive"))
      (node (ref "C2") (pin "2") (pinfunction "2_2") (pintype "passive"))
      (node (ref "C20") (pin "1") (pinfunction "1_1") (pintype "passive"))
      (node (ref "C21") (pin "1") (pinfunction "1_1") (pintype "passive"))
      (node (ref "C22") (pin "1") (pinfunction "1_1") (pintype "passive"))
      (node (ref "C23") (pin "1") (pinfunction "1_1") (pintype "passive"))
      (node (ref "C24") (pin "1") (pinfunction "1_1") (pintype "passive"))
      (node (ref "C25") (pin "1") (pinfunction "1_1") (pintype "passive"))
      (node (ref "C26") (pin "1") (pinfunction "1_1") (pintype "passive"))
      (node (ref "C27") (pin "2") (pinfunction "2_2") (pintype "passive"))
      (node (ref "C28") (pin "1") (pinfunction "1_1") (pintype "passive"))
      (node (ref "C29") (pin "1") (pinfunction "1_1") (pintype "passive"))
      (node (ref "C3") (pin "1") (pinfunction "1_1") (pintype "passive"))
      (node (ref "C30") (pin "1") (pinfunction "1_1") (pintype "passive"))
      (node (ref "C31") (pin "1") (pinfunction "1_1") (pintype "passive"))
      (node (ref "C32") (pin "1") (pinfunction "1_1") (pintype "passive"))
      (node (ref "C33") (pin "1") (pinfunction "1_1") (pintype "passive"))
      (node (ref "C4") (pin "1") (pinfunction "1_1") (pintype "passive"))
      (node (ref "C5") (pin "1") (pinfunction "1_1") (pintype "passive"))
      (node (ref "C56") (pin "1") (pinfunction "1_1") (pintype "passive"))
      (node (ref "C6") (pin "1") (pinfunction "1_1") (pintype "passive"))
      (node (ref "C7") (pin "1") (pinfunction "1_1") (pintype "passive"))
      (node (ref "C8") (pin "1") (pinfunction "1_1") (pintype "passive"))
      (node (ref "C9") (pin "1") (pinfunction "1_1") (pintype "passive"))
      (node (ref "IC1") (pin "1") (pinfunction "GND_1") (pintype "power_in"))
      (node (ref "IC2") (pin "1") (pinfunction "(-)IN_1") (pintype "power_in"))
      (node (ref "IC2") (pin "4") (pinfunction "HV_RTN_4") (pintype "power_in"))
      (node (ref "IC3") (pin "1") (pinfunction "(-)IN_1") (pintype "power_in"))
      (node (ref "IC3") (pin "3") (pinfunction "HV_OUT_3") (pintype "power_in"))
      (node (ref "IC4") (pin "2") (pinfunction "GND_2") (pintype "power_in"))
      (node (ref "IC5") (pin "1") (pinfunction "PGND_1") (pintype "power_in"))
      (node (ref "IC5") (pin "15") (pinfunction "AGND_15") (pintype "power_in"))
      (node (ref "IC6") (pin "2") (pinfunction "GND_2") (pintype "power_in"))
      (node (ref "IC7") (pin "1") (pinfunction "GND_1") (pintype "power_in"))
      (node (ref "L7") (pin "1") (pinfunction "1_1") (pintype "passive"))
      (node (ref "R11") (pin "1") (pinfunction "1_1") (pintype "passive"))
      (node (ref "R125") (pin "1") (pinfunction "1_1") (pintype "passive"))
      (node (ref "R130") (pin "2") (pinfunction "2_2") (pintype "passive"))
      (node (ref "R18") (pin "1") (pinfunction "1_1") (pintype "passive"))
      (node (ref "R21") (pin "2") (pinfunction "2_2") (pintype "passive"))
      (node (ref "R22") (pin "1") (pinfunction "1_1") (pintype "passive"))
      (node (ref "R23") (pin "2") (pinfunction "2_2") (pintype "passive"))
      (node (ref "R32") (pin "1") (pinfunction "1_1") (pintype "passive"))
      (node (ref "R5") (pin "1") (pinfunction "1_1") (pintype "passive"))
      (node (ref "T1") (pin "2") (pinfunction "S_2") (pintype "passive"))
      (node (ref "T3") (pin "2") (pinfunction "S_2") (pintype "passive"))
    )
    (net (code "8") (name "N2kV0") (class "Default")
      (node (ref "C14") (pin "1") (pinfunction "1_1") (pintype "passive"))
      (node (ref "R7") (pin "2") (pinfunction "2_2") (pintype "passive"))
    )
    (net (code "9") (name "N14V0") (class "Default")
      (node (ref "C33") (pin "2") (pinfunction "2_2") (pintype "passive"))
      (node (ref "IC7") (pin "5") (pinfunction "VOUT_5") (pintype "power_in"))
      (node (ref "R30") (pin "2") (pinfunction "2_2") (pintype "passive"))
    )
    (net (code "10") (name "N15V0") (class "Default")
      (node (ref "C32") (pin "2") (pinfunction "2_2") (pintype "passive"))
      (node (ref "L6") (pin "2") (pinfunction "2_2") (pintype "passive"))
      (node (ref "R28") (pin "2") (pinfunction "2_2") (pintype "passive"))
      (node (ref "R29") (pin "1") (pinfunction "1_1") (pintype "passive"))
      (node (ref "R31") (pin "2") (pinfunction "2_2") (pintype "passive"))
    )
    (net (code "11") (name "Net-(C4-Pad2)") (class "Default")
      (node (ref "C4") (pin "2") (pinfunction "2_2") (pintype "passive"))
      (node (ref "R1") (pin "2") (pinfunction "2_2") (pintype "passive"))
      (node (ref "R2") (pin "1") (pinfunction "1_1") (pintype "passive"))
    )
    (net (code "12") (name "Net-(C13-Pad1)") (class "Default")
      (node (ref "C13") (pin "1") (pinfunction "1_1") (pintype "passive"))
      (node (ref "R6") (pin "2") (pinfunction "2_2") (pintype "passive"))
      (node (ref "R7") (pin "1") (pinfunction "1_1") (pintype "passive"))
    )
    (net (code "13") (name "Net-(C20-Pad2)") (class "Default")
      (node (ref "C20") (pin "2") (pinfunction "2_2") (pintype "passive"))
      (node (ref "R14") (pin "1") (pinfunction "1_1") (pintype "passive"))
    )
    (net (code "14") (name "Net-(C26-Pad2)") (class "Default")
      (node (ref "C26") (pin "2") (pinfunction "2_2") (pintype "passive"))
      (node (ref "R19") (pin "1") (pinfunction "1_1") (pintype "passive"))
    )
    (net (code "15") (name "Net-(D1-A)") (class "Default")
      (node (ref "D1") (pin "2") (pinfunction "A_2") (pintype "passive"))
      (node (ref "IC5") (pin "2") (pinfunction "SW1_2") (pintype "output"))
      (node (ref "L4") (pin "2") (pinfunction "2_2") (pintype "passive"))
    )
    (net (code "16") (name "Net-(D1-C)") (class "Default")
      (node (ref "C21") (pin "2") (pinfunction "2_2") (pintype "passive"))
      (node (ref "D1") (pin "1") (pinfunction "C_1") (pintype "passive"))
      (node (ref "L5") (pin "1") (pinfunction "1_1") (pintype "passive"))
      (node (ref "R12") (pin "1") (pinfunction "1_1") (pintype "passive"))
    )
    (net (code "17") (name "Net-(D2-A)") (class "Default")
      (node (ref "C31") (pin "2") (pinfunction "2_2") (pintype "passive"))
      (node (ref "D2") (pin "2") (pinfunction "A_2") (pintype "passive"))
      (node (ref "L6") (pin "1") (pinfunction "1_1") (pintype "passive"))
      (node (ref "R31") (pin "1") (pinfunction "1_1") (pintype "passive"))
    )
    (net (code "18") (name "Net-(D2-C)") (class "Default")
      (node (ref "D2") (pin "1") (pinfunction "C_1") (pintype "passive"))
      (node (ref "IC5") (pin "20") (pinfunction "SW2_20") (pintype "output"))
      (node (ref "L7") (pin "2") (pinfunction "2_2") (pintype "passive"))
    )
    (net (code "19") (name "Net-(IC2-CTRL)") (class "Default")
      (node (ref "IC2") (pin "5") (pinfunction "CTRL_5") (pintype "input"))
      (node (ref "IC3") (pin "5") (pinfunction "CTRL_5") (pintype "input"))
      (node (ref "R4") (pin "2") (pinfunction "2_2") (pintype "passive"))
      (node (ref "T1") (pin "3") (pinfunction "D_3") (pintype "passive"))
    )
    (net (code "20") (name "Net-(IC2-HV_OUT)") (class "Default")
      (node (ref "C3") (pin "2") (pinfunction "2_2") (pintype "passive"))
      (node (ref "IC2") (pin "3") (pinfunction "HV_OUT_3") (pintype "power_in"))
      (node (ref "R1") (pin "1") (pinfunction "1_1") (pintype "passive"))
      (node (ref "R127") (pin "2") (pinfunction "2_2") (pintype "passive"))
    )
    (net (code "21") (name "Net-(IC3-HV_RTN)") (class "Default")
      (node (ref "C12") (pin "1") (pinfunction "1_1") (pintype "passive"))
      (node (ref "IC3") (pin "4") (pinfunction "HV_RTN_4") (pintype "power_in"))
      (node (ref "R128") (pin "1") (pinfunction "1_1") (pintype "passive"))
      (node (ref "R6") (pin "1") (pinfunction "1_1") (pintype "passive"))
    )
    (net (code "22") (name "Net-(IC4-EN)") (class "Default")
      (node (ref "C17") (pin "2") (pinfunction "2_2") (pintype "passive"))
      (node (ref "IC4") (pin "1") (pinfunction "VIN_1") (pintype "power_in"))
      (node (ref "IC4") (pin "3") (pinfunction "EN_3") (pintype "input"))
      (node (ref "R9") (pin "2") (pinfunction "2_2") (pintype "passive"))
    )
    (net (code "23") (name "Net-(IC4-SENSE{slash}ADJ)") (class "Default")
      (node (ref "IC4") (pin "4") (pinfunction "SENSE/ADJ_4") (pintype "input"))
      (node (ref "R10") (pin "1") (pinfunction "1_1") (pintype "passive"))
      (node (ref "R11") (pin "2") (pinfunction "2_2") (pintype "passive"))
    )
    (net (code "24") (name "Net-(IC5-COMP1)") (class "Default")
      (node (ref "C19") (pin "2") (pinfunction "2_2") (pintype "passive"))
      (node (ref "IC5") (pin "8") (pinfunction "COMP1_8") (pintype "input"))
      (node (ref "R14") (pin "2") (pinfunction "2_2") (pintype "passive"))
    )
    (net (code "25") (name "Net-(IC5-COMP2)") (class "Default")
      (node (ref "C24") (pin "2") (pinfunction "2_2") (pintype "passive"))
      (node (ref "IC5") (pin "12") (pinfunction "COMP2_12") (pintype "input"))
      (node (ref "R19") (pin "2") (pinfunction "2_2") (pintype "passive"))
    )
    (net (code "26") (name "Net-(IC5-EN1)") (class "Default")
      (node (ref "IC5") (pin "11") (pinfunction "EN2_11") (pintype "input"))
      (node (ref "IC5") (pin "9") (pinfunction "EN1_9") (pintype "input"))
      (node (ref "R13") (pin "1") (pinfunction "1_1") (pintype "passive"))
    )
    (net (code "27") (name "Net-(IC5-FB1)") (class "Default")
      (node (ref "IC5") (pin "7") (pinfunction "FB1_7") (pintype "input"))
      (node (ref "R20") (pin "1") (pinfunction "1_1") (pintype "passive"))
      (node (ref "R22") (pin "2") (pinfunction "2_2") (pintype "passive"))
    )
    (net (code "28") (name "Net-(IC5-FB2)") (class "Default")
      (node (ref "IC5") (pin "13") (pinfunction "FB2_13") (pintype "input"))
      (node (ref "R27") (pin "1") (pinfunction "1_1") (pintype "passive"))
      (node (ref "R28") (pin "1") (pinfunction "1_1") (pintype "passive"))
    )
    (net (code "29") (name "Net-(IC5-INBK)") (class "Default")
      (node (ref "IC5") (pin "3") (pinfunction "INBK_3") (pintype "output"))
      (node (ref "L4") (pin "1") (pinfunction "1_1") (pintype "passive"))
    )
    (net (code "30") (name "Net-(IC5-SEQ)") (class "Default")
      (node (ref "IC5") (pin "5") (pinfunction "SEQ_5") (pintype "input"))
      (node (ref "R25") (pin "1") (pinfunction "1_1") (pintype "passive"))
    )
    (net (code "31") (name "Net-(IC5-SLEW)") (class "Default")
      (node (ref "IC5") (pin "6") (pinfunction "SLEW_6") (pintype "input"))
      (node (ref "R26") (pin "1") (pinfunction "1_1") (pintype "passive"))
    )
    (net (code "32") (name "Net-(IC5-SS)") (class "Default")
      (node (ref "IC5") (pin "10") (pinfunction "SS_10") (pintype "input"))
      (node (ref "R21") (pin "1") (pinfunction "1_1") (pintype "passive"))
    )
    (net (code "33") (name "Net-(IC5-SYNC{slash}FREQ)") (class "Default")
      (node (ref "IC5") (pin "4") (pinfunction "SYNC/FREQ_4") (pintype "input"))
      (node (ref "R24") (pin "1") (pinfunction "1_1") (pintype "passive"))
    )
    (net (code "34") (name "Net-(IC5-VREF)") (class "Default")
      (node (ref "C27") (pin "1") (pinfunction "1_1") (pintype "passive"))
      (node (ref "IC5") (pin "14") (pinfunction "VREF_14") (pintype "output"))
      (node (ref "R27") (pin "2") (pinfunction "2_2") (pintype "passive"))
    )
    (net (code "35") (name "Net-(IC5-VREG)") (class "Default")
      (node (ref "C28") (pin "2") (pinfunction "2_2") (pintype "passive"))
      (node (ref "IC5") (pin "16") (pinfunction "VREG_16") (pintype "output"))
      (node (ref "R24") (pin "2") (pinfunction "2_2") (pintype "passive"))
      (node (ref "R25") (pin "2") (pinfunction "2_2") (pintype "passive"))
      (node (ref "R26") (pin "2") (pinfunction "2_2") (pintype "passive"))
    )
    (net (code "36") (name "Net-(IC6-EN)") (class "Default")
      (node (ref "C23") (pin "2") (pinfunction "2_2") (pintype "passive"))
      (node (ref "IC6") (pin "1") (pinfunction "VIN_1") (pintype "power_in"))
      (node (ref "IC6") (pin "3") (pinfunction "EN_3") (pintype "input"))
      (node (ref "R15") (pin "2") (pinfunction "2_2") (pintype "passive"))
    )
    (net (code "37") (name "Net-(IC6-SENSE{slash}ADJ)") (class "Default")
      (node (ref "IC6") (pin "4") (pinfunction "SENSE/ADJ_4") (pintype "input"))
      (node (ref "R16") (pin "1") (pinfunction "1_1") (pintype "passive"))
      (node (ref "R18") (pin "2") (pinfunction "2_2") (pintype "passive"))
    )
    (net (code "38") (name "Net-(IC7-ADJ)") (class "Default")
      (node (ref "IC7") (pin "4") (pinfunction "ADJ_4") (pintype "input"))
      (node (ref "R30") (pin "1") (pinfunction "1_1") (pintype "passive"))
      (node (ref "R32") (pin "2") (pinfunction "2_2") (pintype "passive"))
    )
    (net (code "39") (name "Net-(IC7-EN)") (class "Default")
      (node (ref "C30") (pin "2") (pinfunction "2_2") (pintype "passive"))
      (node (ref "IC7") (pin "2") (pinfunction "VIN_2") (pintype "input"))
      (node (ref "IC7") (pin "3") (pinfunction "EN_3") (pintype "input"))
      (node (ref "R29") (pin "2") (pinfunction "2_2") (pintype "passive"))
    )
    (net (code "40") (name "Net-(R125-Pad2)") (class "Default")
      (node (ref "R125") (pin "2") (pinfunction "2_2") (pintype "passive"))
      (node (ref "R126") (pin "1") (pinfunction "1_1") (pintype "passive"))
    )
    (net (code "41") (name "Net-(R126-Pad2)") (class "Default")
      (node (ref "R126") (pin "2") (pinfunction "2_2") (pintype "passive"))
      (node (ref "R127") (pin "1") (pinfunction "1_1") (pintype "passive"))
    )
    (net (code "42") (name "Net-(R128-Pad2)") (class "Default")
      (node (ref "R128") (pin "2") (pinfunction "2_2") (pintype "passive"))
      (node (ref "R129") (pin "1") (pinfunction "1_1") (pintype "passive"))
    )
    (net (code "43") (name "Net-(R129-Pad2)") (class "Default")
      (node (ref "R129") (pin "2") (pinfunction "2_2") (pintype "passive"))
      (node (ref "R130") (pin "1") (pinfunction "1_1") (pintype "passive"))
    )
    (net (code "44") (name "Net-(T2-G)") (class "Default")
      (node (ref "R17") (pin "1") (pinfunction "1_1") (pintype "passive"))
      (node (ref "T2") (pin "1") (pinfunction "G_1") (pintype "passive"))
      (node (ref "T3") (pin "3") (pinfunction "D_3") (pintype "passive"))
    )
    (net (code "45") (name "P2kV0") (class "Default")
      (node (ref "C5") (pin "2") (pinfunction "2_2") (pintype "passive"))
      (node (ref "R2") (pin "2") (pinfunction "2_2") (pintype "passive"))
    )
    (net (code "46") (name "P3V3") (class "Default")
      (node (ref "R13") (pin "2") (pinfunction "2_2") (pintype "passive"))
      (node (ref "R17") (pin "2") (pinfunction "2_2") (pintype "passive"))
      (node (ref "R8") (pin "2") (pinfunction "2_2") (pintype "passive"))
      (node (ref "T2") (pin "2") (pinfunction "S_2") (pintype "passive"))
    )
    (net (code "47") (name "P3V3_DAC") (class "Default")
      (node (ref "T2") (pin "3") (pinfunction "D_3") (pintype "passive"))
    )
    (net (code "48") (name "P5V0A") (class "Default")
      (node (ref "C18") (pin "2") (pinfunction "2_2") (pintype "passive"))
      (node (ref "IC4") (pin "5") (pinfunction "VOUT_5") (pintype "power_in"))
      (node (ref "R10") (pin "2") (pinfunction "2_2") (pintype "passive"))
    )
    (net (code "49") (name "P12V0") (class "Default")
      (node (ref "C29") (pin "2") (pinfunction "2_2") (pintype "passive"))
      (node (ref "C56") (pin "2") (pinfunction "2_2") (pintype "passive"))
      (node (ref "C7") (pin "2") (pinfunction "2_2") (pintype "passive"))
      (node (ref "C8") (pin "2") (pinfunction "2_2") (pintype "passive"))
      (node (ref "IC1") (pin "3") (pinfunction "VIN_3") (pintype "input"))
      (node (ref "IC5") (pin "17") (pinfunction "PVIN1_17") (pintype "power_in"))
      (node (ref "IC5") (pin "18") (pinfunction "PVINSYSS_18") (pintype "power_in"))
      (node (ref "IC5") (pin "19") (pinfunction "PVIN2_19") (pintype "power_in"))
      (node (ref "L3") (pin "2") (pinfunction "2_2") (pintype "passive"))
      (node (ref "R9") (pin "1") (pinfunction "1_1") (pintype "passive"))
    )
    (net (code "50") (name "P12V0_IN") (class "Default")
      (node (ref "C6") (pin "2") (pinfunction "2_2") (pintype "passive"))
      (node (ref "L3") (pin "1") (pinfunction "1_1") (pintype "passive"))
    )
    (net (code "51") (name "P14V0") (class "Default")
      (node (ref "C25") (pin "2") (pinfunction "2_2") (pintype "passive"))
      (node (ref "IC6") (pin "5") (pinfunction "VOUT_5") (pintype "power_in"))
      (node (ref "R16") (pin "2") (pinfunction "2_2") (pintype "passive"))
      (node (ref "R23") (pin "1") (pinfunction "1_1") (pintype "passive"))
      (node (ref "T3") (pin "1") (pinfunction "G_1") (pintype "passive"))
    )
    (net (code "52") (name "P15V0") (class "Default")
      (node (ref "C22") (pin "2") (pinfunction "2_2") (pintype "passive"))
      (node (ref "L5") (pin "2") (pinfunction "2_2") (pintype "passive"))
      (node (ref "R12") (pin "2") (pinfunction "2_2") (pintype "passive"))
      (node (ref "R15") (pin "1") (pinfunction "1_1") (pintype "passive"))
      (node (ref "R20") (pin "2") (pinfunction "2_2") (pintype "passive"))
    )
    (net (code "53") (name "unconnected-(IC1-EN-Pad5)") (class "Default")
      (node (ref "IC1") (pin "5") (pinfunction "EN_5") (pintype "input+no_connect"))
    )
  )
)
